# ArduinoUhr_VFD_2.net
KiCad netlist of a schematic drawn in EAGLE
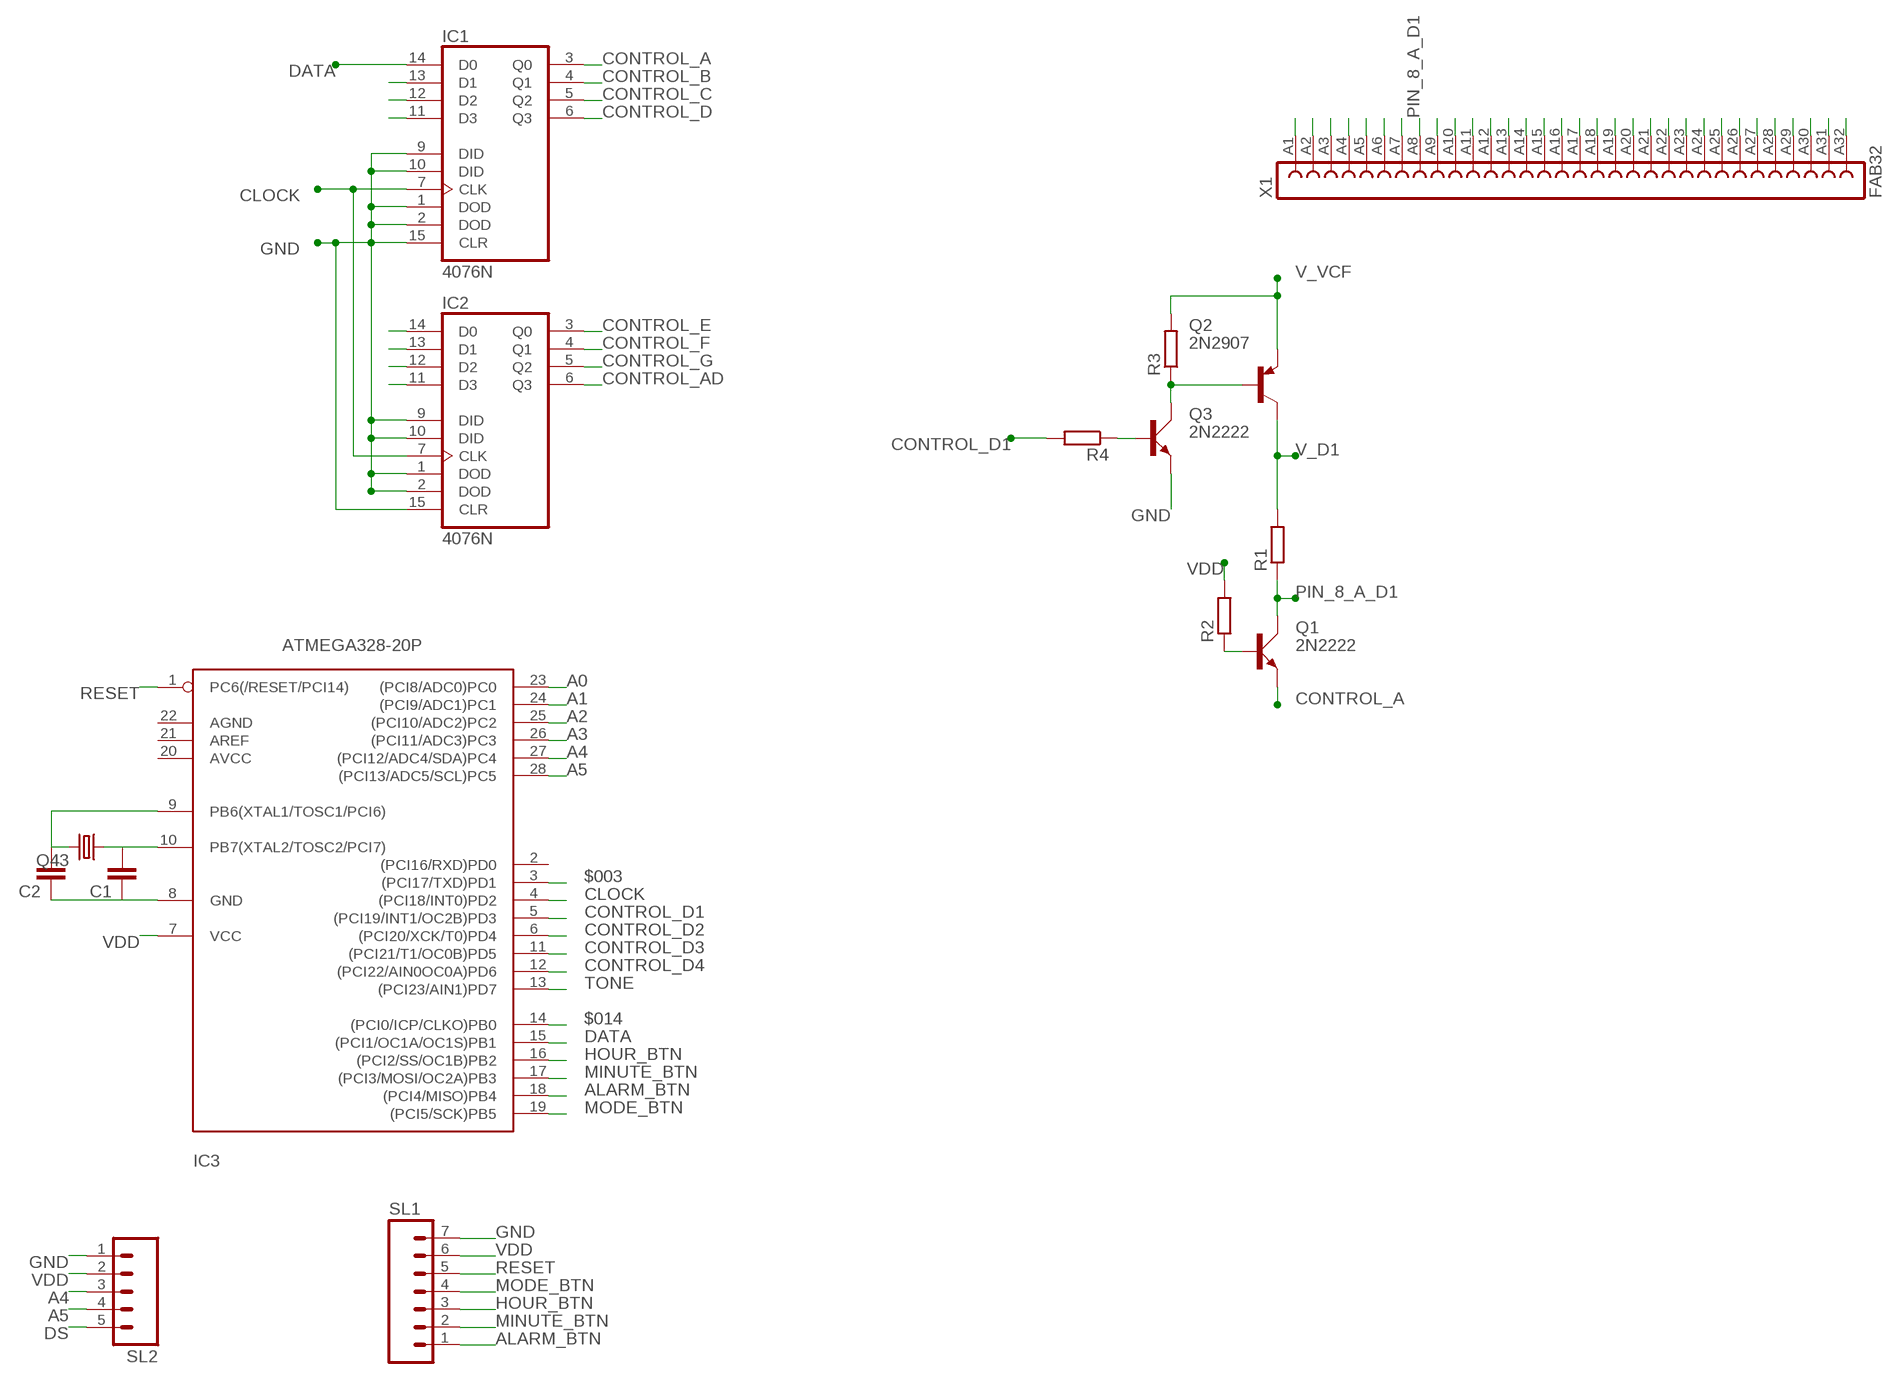
[diagram p0: schematic, sheet 1]

(export (version "E")
  (design (tool "Eeschema 10.0.6"))
  (components
    (comp (ref "C1")
      (value "C-EU025-024X044")
      (footprint "eagle-import:C025-024X044")
      (libsource (lib "eagle-import") (part "C-EU025-024X044"))
    )
    (comp (ref "C2")
      (value "C-EU025-024X044")
      (footprint "eagle-import:C025-024X044")
      (libsource (lib "eagle-import") (part "C-EU025-024X044"))
    )
    (comp (ref "IC1")
      (value "4076N")
      (footprint "eagle-import:DIL16")
      (libsource (lib "eagle-import") (part "4076N"))
    )
    (comp (ref "IC2")
      (value "4076N")
      (footprint "eagle-import:DIL16")
      (libsource (lib "eagle-import") (part "4076N"))
    )
    (comp (ref "IC3")
      (value "ATMEGA328-20P")
      (footprint "eagle-import:DIL28-3")
      (libsource (lib "eagle-import") (part "ATMEGA328P-20"))
    )
    (comp (ref "Q1")
      (value "2N2222")
      (footprint "eagle-import:TO18A")
      (libsource (lib "eagle-import") (part "2N2222"))
    )
    (comp (ref "Q2")
      (value "2N2907")
      (footprint "eagle-import:TO18")
      (libsource (lib "eagle-import") (part "2N2907"))
    )
    (comp (ref "Q3")
      (value "2N2222")
      (footprint "eagle-import:TO18A")
      (libsource (lib "eagle-import") (part "2N2222"))
    )
    (comp (ref "Q43")
      (value "CRYSTALHC49S")
      (footprint "eagle-import:HC49_S")
      (libsource (lib "eagle-import") (part "CRYSTALHC49S"))
    )
    (comp (ref "R1")
      (value "R-EU_0204/7")
      (footprint "eagle-import:0204_7")
      (libsource (lib "eagle-import") (part "R-EU_0204/7"))
    )
    (comp (ref "R2")
      (value "R-EU_0204/7")
      (footprint "eagle-import:0204_7")
      (libsource (lib "eagle-import") (part "R-EU_0204/7"))
    )
    (comp (ref "R3")
      (value "R-EU_0204/7")
      (footprint "eagle-import:0204_7")
      (libsource (lib "eagle-import") (part "R-EU_0204/7"))
    )
    (comp (ref "R4")
      (value "R-EU_0204/7")
      (footprint "eagle-import:0204_7")
      (libsource (lib "eagle-import") (part "R-EU_0204/7"))
    )
    (comp (ref "SL1")
      (value "M07")
      (footprint "eagle-import:07P")
      (libsource (lib "eagle-import") (part "M07"))
    )
    (comp (ref "SL2")
      (value "M05")
      (footprint "eagle-import:05P")
      (libsource (lib "eagle-import") (part "M05"))
    )
    (comp (ref "X1")
      (value "FAB32")
      (footprint "eagle-import:FAB32")
      (libsource (lib "eagle-import") (part "FAB32"))
    )
  )
  (nets
    (net (code "1") (name "/$003") (class "Default")
      (node (ref "IC3") (pin "3") (pinfunction "(PCI17/TXD)PD1_3") (pintype "bidirectional"))
    )
    (net (code "2") (name "/$014") (class "Default")
      (node (ref "IC3") (pin "14") (pinfunction "(PCI0/ICP/CLKO)PB0_14") (pintype "bidirectional"))
    )
    (net (code "3") (name "/A0") (class "Default")
      (node (ref "IC3") (pin "23") (pinfunction "(PCI8/ADC0)PC0_23") (pintype "bidirectional"))
    )
    (net (code "4") (name "/A1") (class "Default")
      (node (ref "IC3") (pin "24") (pinfunction "(PCI9/ADC1)PC1_24") (pintype "bidirectional"))
    )
    (net (code "5") (name "/A2") (class "Default")
      (node (ref "IC3") (pin "25") (pinfunction "(PCI10/ADC2)PC2_25") (pintype "bidirectional"))
    )
    (net (code "6") (name "/A3") (class "Default")
      (node (ref "IC3") (pin "26") (pinfunction "(PCI11/ADC3)PC3_26") (pintype "bidirectional"))
    )
    (net (code "7") (name "/A4") (class "Default")
      (node (ref "IC3") (pin "27") (pinfunction "(PCI12/ADC4/SDA)PC4_27") (pintype "bidirectional"))
      (node (ref "SL2") (pin "3") (pinfunction "3_3") (pintype "passive"))
    )
    (net (code "8") (name "/A5") (class "Default")
      (node (ref "IC3") (pin "28") (pinfunction "(PCI13/ADC5/SCL)PC5_28") (pintype "bidirectional"))
      (node (ref "SL2") (pin "4") (pinfunction "4_4") (pintype "passive"))
    )
    (net (code "9") (name "/ALARM_BTN") (class "Default")
      (node (ref "IC3") (pin "18") (pinfunction "(PCI4/MISO)PB4_18") (pintype "bidirectional"))
      (node (ref "SL1") (pin "1") (pinfunction "1_1") (pintype "passive"))
    )
    (net (code "10") (name "/CLOCK") (class "Default")
      (node (ref "IC1") (pin "7") (pinfunction "CLK_7") (pintype "input"))
      (node (ref "IC2") (pin "7") (pinfunction "CLK_7") (pintype "input"))
      (node (ref "IC3") (pin "4") (pinfunction "(PCI18/INT0)PD2_4") (pintype "bidirectional"))
    )
    (net (code "11") (name "/CONTROL_A") (class "Default")
      (node (ref "IC1") (pin "13") (pinfunction "D1_13") (pintype "input"))
      (node (ref "IC1") (pin "3") (pinfunction "Q0_3") (pintype "output"))
      (node (ref "Q1") (pin "E") (pinfunction "E_E") (pintype "passive"))
    )
    (net (code "12") (name "/CONTROL_AD") (class "Default")
      (node (ref "IC2") (pin "6") (pinfunction "Q3_6") (pintype "output"))
    )
    (net (code "13") (name "/CONTROL_B") (class "Default")
      (node (ref "IC1") (pin "12") (pinfunction "D2_12") (pintype "input"))
      (node (ref "IC1") (pin "4") (pinfunction "Q1_4") (pintype "output"))
    )
    (net (code "14") (name "/CONTROL_C") (class "Default")
      (node (ref "IC1") (pin "11") (pinfunction "D3_11") (pintype "input"))
      (node (ref "IC1") (pin "5") (pinfunction "Q2_5") (pintype "output"))
    )
    (net (code "15") (name "/CONTROL_D") (class "Default")
      (node (ref "IC1") (pin "6") (pinfunction "Q3_6") (pintype "output"))
      (node (ref "IC2") (pin "14") (pinfunction "D0_14") (pintype "input"))
    )
    (net (code "16") (name "/CONTROL_D1") (class "Default")
      (node (ref "IC3") (pin "5") (pinfunction "(PCI19/INT1/OC2B)PD3_5") (pintype "bidirectional"))
      (node (ref "R4") (pin "2") (pinfunction "2_2") (pintype "passive"))
    )
    (net (code "17") (name "/CONTROL_D2") (class "Default")
      (node (ref "IC3") (pin "6") (pinfunction "(PCI20/XCK/T0)PD4_6") (pintype "bidirectional"))
    )
    (net (code "18") (name "/CONTROL_D3") (class "Default")
      (node (ref "IC3") (pin "11") (pinfunction "(PCI21/T1/OC0B)PD5_11") (pintype "bidirectional"))
    )
    (net (code "19") (name "/CONTROL_D4") (class "Default")
      (node (ref "IC3") (pin "12") (pinfunction "(PCI22/AIN0OC0A)PD6_12") (pintype "bidirectional"))
    )
    (net (code "20") (name "/CONTROL_E") (class "Default")
      (node (ref "IC2") (pin "13") (pinfunction "D1_13") (pintype "input"))
      (node (ref "IC2") (pin "3") (pinfunction "Q0_3") (pintype "output"))
    )
    (net (code "21") (name "/CONTROL_F") (class "Default")
      (node (ref "IC2") (pin "12") (pinfunction "D2_12") (pintype "input"))
      (node (ref "IC2") (pin "4") (pinfunction "Q1_4") (pintype "output"))
    )
    (net (code "22") (name "/CONTROL_G") (class "Default")
      (node (ref "IC2") (pin "11") (pinfunction "D3_11") (pintype "input"))
      (node (ref "IC2") (pin "5") (pinfunction "Q2_5") (pintype "output"))
    )
    (net (code "23") (name "/DATA") (class "Default")
      (node (ref "IC1") (pin "14") (pinfunction "D0_14") (pintype "input"))
      (node (ref "IC3") (pin "15") (pinfunction "(PCI1/OC1A/OC1S)PB1_15") (pintype "bidirectional"))
    )
    (net (code "24") (name "/DS") (class "Default")
      (node (ref "SL2") (pin "5") (pinfunction "5_5") (pintype "passive"))
    )
    (net (code "25") (name "/GND") (class "Default")
      (node (ref "C1") (pin "1") (pinfunction "1_1") (pintype "passive"))
      (node (ref "C2") (pin "1") (pinfunction "1_1") (pintype "passive"))
      (node (ref "IC1") (pin "1") (pinfunction "DOD_1") (pintype "input"))
      (node (ref "IC1") (pin "10") (pinfunction "DID_10") (pintype "input"))
      (node (ref "IC1") (pin "15") (pinfunction "CLR_15") (pintype "input"))
      (node (ref "IC1") (pin "2") (pinfunction "DOD_2") (pintype "input"))
      (node (ref "IC1") (pin "9") (pinfunction "DID_9") (pintype "input"))
      (node (ref "IC2") (pin "1") (pinfunction "DOD_1") (pintype "input"))
      (node (ref "IC2") (pin "10") (pinfunction "DID_10") (pintype "input"))
      (node (ref "IC2") (pin "15") (pinfunction "CLR_15") (pintype "input"))
      (node (ref "IC2") (pin "2") (pinfunction "DOD_2") (pintype "input"))
      (node (ref "IC2") (pin "9") (pinfunction "DID_9") (pintype "input"))
      (node (ref "IC3") (pin "8") (pinfunction "GND_8") (pintype "bidirectional"))
      (node (ref "Q3") (pin "E") (pinfunction "E_E") (pintype "passive"))
      (node (ref "SL1") (pin "7") (pinfunction "7_7") (pintype "passive"))
      (node (ref "SL2") (pin "1") (pinfunction "1_1") (pintype "passive"))
    )
    (net (code "26") (name "/HOUR_BTN") (class "Default")
      (node (ref "IC3") (pin "16") (pinfunction "(PCI2/SS/OC1B)PB2_16") (pintype "bidirectional"))
      (node (ref "SL1") (pin "3") (pinfunction "3_3") (pintype "passive"))
    )
    (net (code "27") (name "/MINUTE_BTN") (class "Default")
      (node (ref "IC3") (pin "17") (pinfunction "(PCI3/MOSI/OC2A)PB3_17") (pintype "bidirectional"))
      (node (ref "SL1") (pin "2") (pinfunction "2_2") (pintype "passive"))
    )
    (net (code "28") (name "/MODE_BTN") (class "Default")
      (node (ref "IC3") (pin "19") (pinfunction "(PCI5/SCK)PB5_19") (pintype "bidirectional"))
      (node (ref "SL1") (pin "4") (pinfunction "4_4") (pintype "passive"))
    )
    (net (code "29") (name "/PIN_8_A_D1") (class "Default")
      (node (ref "Q1") (pin "C") (pinfunction "C_C") (pintype "passive"))
      (node (ref "R1") (pin "1") (pinfunction "1_1") (pintype "passive"))
      (node (ref "X1") (pin "A8") (pinfunction "8_A8") (pintype "passive"))
    )
    (net (code "30") (name "/RESET") (class "Default")
      (node (ref "IC3") (pin "1") (pinfunction "PC6(/RESET/PCI14)_1") (pintype "bidirectional"))
      (node (ref "SL1") (pin "5") (pinfunction "5_5") (pintype "passive"))
    )
    (net (code "31") (name "/TONE") (class "Default")
      (node (ref "IC3") (pin "13") (pinfunction "(PCI23/AIN1)PD7_13") (pintype "bidirectional"))
    )
    (net (code "32") (name "/VDD") (class "Default")
      (node (ref "IC3") (pin "7") (pinfunction "VCC_7") (pintype "bidirectional"))
      (node (ref "R2") (pin "2") (pinfunction "2_2") (pintype "passive"))
      (node (ref "SL1") (pin "6") (pinfunction "6_6") (pintype "passive"))
      (node (ref "SL2") (pin "2") (pinfunction "2_2") (pintype "passive"))
    )
    (net (code "33") (name "/V_D1") (class "Default")
      (node (ref "Q2") (pin "3") (pinfunction "C_3") (pintype "passive"))
      (node (ref "R1") (pin "2") (pinfunction "2_2") (pintype "passive"))
    )
    (net (code "34") (name "/V_VCF") (class "Default")
      (node (ref "Q2") (pin "1") (pinfunction "E_1") (pintype "passive"))
      (node (ref "R3") (pin "2") (pinfunction "2_2") (pintype "passive"))
    )
    (net (code "35") (name "Net-(IC3-PB6(XTAL1{slash}TOSC1{slash}PCI6))") (class "Default")
      (node (ref "C2") (pin "2") (pinfunction "2_2") (pintype "passive"))
      (node (ref "IC3") (pin "9") (pinfunction "PB6(XTAL1/TOSC1/PCI6)_9") (pintype "bidirectional"))
      (node (ref "Q43") (pin "2") (pinfunction "2_2") (pintype "passive"))
    )
    (net (code "36") (name "Net-(IC3-PB7(XTAL2{slash}TOSC2{slash}PCI7))") (class "Default")
      (node (ref "C1") (pin "2") (pinfunction "2_2") (pintype "passive"))
      (node (ref "IC3") (pin "10") (pinfunction "PB7(XTAL2/TOSC2/PCI7)_10") (pintype "bidirectional"))
      (node (ref "Q43") (pin "1") (pinfunction "1_1") (pintype "passive"))
    )
    (net (code "37") (name "Net-(Q1-PadB)") (class "Default")
      (node (ref "Q1") (pin "B") (pinfunction "B_B") (pintype "passive"))
      (node (ref "R2") (pin "1") (pinfunction "1_1") (pintype "passive"))
    )
    (net (code "38") (name "Net-(Q2-B)") (class "Default")
      (node (ref "Q2") (pin "2") (pinfunction "B_2") (pintype "passive"))
      (node (ref "Q3") (pin "C") (pinfunction "C_C") (pintype "passive"))
      (node (ref "R3") (pin "1") (pinfunction "1_1") (pintype "passive"))
    )
    (net (code "39") (name "Net-(Q3-PadB)") (class "Default")
      (node (ref "Q3") (pin "B") (pinfunction "B_B") (pintype "passive"))
      (node (ref "R4") (pin "1") (pinfunction "1_1") (pintype "passive"))
    )
    (net (code "40") (name "unconnected-(IC3-(PCI16{slash}RXD)PD0-Pad2)") (class "Default")
      (node (ref "IC3") (pin "2") (pinfunction "(PCI16/RXD)PD0_2") (pintype "bidirectional"))
    )
    (net (code "41") (name "unconnected-(IC3-AGND-Pad22)") (class "Default")
      (node (ref "IC3") (pin "22") (pinfunction "AGND_22") (pintype "bidirectional"))
    )
    (net (code "42") (name "unconnected-(IC3-AREF-Pad21)") (class "Default")
      (node (ref "IC3") (pin "21") (pinfunction "AREF_21") (pintype "bidirectional"))
    )
    (net (code "43") (name "unconnected-(IC3-AVCC-Pad20)") (class "Default")
      (node (ref "IC3") (pin "20") (pinfunction "AVCC_20") (pintype "bidirectional"))
    )
    (net (code "44") (name "unconnected-(X1-1-PadA1)") (class "Default")
      (node (ref "X1") (pin "A1") (pinfunction "1_A1") (pintype "passive"))
    )
    (net (code "45") (name "unconnected-(X1-2-PadA2)") (class "Default")
      (node (ref "X1") (pin "A2") (pinfunction "2_A2") (pintype "passive"))
    )
    (net (code "46") (name "unconnected-(X1-3-PadA3)") (class "Default")
      (node (ref "X1") (pin "A3") (pinfunction "3_A3") (pintype "passive"))
    )
    (net (code "47") (name "unconnected-(X1-4-PadA4)") (class "Default")
      (node (ref "X1") (pin "A4") (pinfunction "4_A4") (pintype "passive"))
    )
    (net (code "48") (name "unconnected-(X1-5-PadA5)") (class "Default")
      (node (ref "X1") (pin "A5") (pinfunction "5_A5") (pintype "passive"))
    )
    (net (code "49") (name "unconnected-(X1-6-PadA6)") (class "Default")
      (node (ref "X1") (pin "A6") (pinfunction "6_A6") (pintype "passive"))
    )
    (net (code "50") (name "unconnected-(X1-7-PadA7)") (class "Default")
      (node (ref "X1") (pin "A7") (pinfunction "7_A7") (pintype "passive"))
    )
    (net (code "51") (name "unconnected-(X1-9-PadA9)") (class "Default")
      (node (ref "X1") (pin "A9") (pinfunction "9_A9") (pintype "passive"))
    )
    (net (code "52") (name "unconnected-(X1-10-PadA10)") (class "Default")
      (node (ref "X1") (pin "A10") (pinfunction "10_A10") (pintype "passive"))
    )
    (net (code "53") (name "unconnected-(X1-11-PadA11)") (class "Default")
      (node (ref "X1") (pin "A11") (pinfunction "11_A11") (pintype "passive"))
    )
    (net (code "54") (name "unconnected-(X1-12-PadA12)") (class "Default")
      (node (ref "X1") (pin "A12") (pinfunction "12_A12") (pintype "passive"))
    )
    (net (code "55") (name "unconnected-(X1-13-PadA13)") (class "Default")
      (node (ref "X1") (pin "A13") (pinfunction "13_A13") (pintype "passive"))
    )
    (net (code "56") (name "unconnected-(X1-14-PadA14)") (class "Default")
      (node (ref "X1") (pin "A14") (pinfunction "14_A14") (pintype "passive"))
    )
    (net (code "57") (name "unconnected-(X1-15-PadA15)") (class "Default")
      (node (ref "X1") (pin "A15") (pinfunction "15_A15") (pintype "passive"))
    )
    (net (code "58") (name "unconnected-(X1-16-PadA16)") (class "Default")
      (node (ref "X1") (pin "A16") (pinfunction "16_A16") (pintype "passive"))
    )
    (net (code "59") (name "unconnected-(X1-17-PadA17)") (class "Default")
      (node (ref "X1") (pin "A17") (pinfunction "17_A17") (pintype "passive"))
    )
    (net (code "60") (name "unconnected-(X1-18-PadA18)") (class "Default")
      (node (ref "X1") (pin "A18") (pinfunction "18_A18") (pintype "passive"))
    )
    (net (code "61") (name "unconnected-(X1-19-PadA19)") (class "Default")
      (node (ref "X1") (pin "A19") (pinfunction "19_A19") (pintype "passive"))
    )
    (net (code "62") (name "unconnected-(X1-20-PadA20)") (class "Default")
      (node (ref "X1") (pin "A20") (pinfunction "20_A20") (pintype "passive"))
    )
    (net (code "63") (name "unconnected-(X1-21-PadA21)") (class "Default")
      (node (ref "X1") (pin "A21") (pinfunction "21_A21") (pintype "passive"))
    )
    (net (code "64") (name "unconnected-(X1-22-PadA22)") (class "Default")
      (node (ref "X1") (pin "A22") (pinfunction "22_A22") (pintype "passive"))
    )
    (net (code "65") (name "unconnected-(X1-23-PadA23)") (class "Default")
      (node (ref "X1") (pin "A23") (pinfunction "23_A23") (pintype "passive"))
    )
    (net (code "66") (name "unconnected-(X1-24-PadA24)") (class "Default")
      (node (ref "X1") (pin "A24") (pinfunction "24_A24") (pintype "passive"))
    )
    (net (code "67") (name "unconnected-(X1-25-PadA25)") (class "Default")
      (node (ref "X1") (pin "A25") (pinfunction "25_A25") (pintype "passive"))
    )
    (net (code "68") (name "unconnected-(X1-26-PadA26)") (class "Default")
      (node (ref "X1") (pin "A26") (pinfunction "26_A26") (pintype "passive"))
    )
    (net (code "69") (name "unconnected-(X1-27-PadA27)") (class "Default")
      (node (ref "X1") (pin "A27") (pinfunction "27_A27") (pintype "passive"))
    )
    (net (code "70") (name "unconnected-(X1-28-PadA28)") (class "Default")
      (node (ref "X1") (pin "A28") (pinfunction "28_A28") (pintype "passive"))
    )
    (net (code "71") (name "unconnected-(X1-29-PadA29)") (class "Default")
      (node (ref "X1") (pin "A29") (pinfunction "29_A29") (pintype "passive"))
    )
    (net (code "72") (name "unconnected-(X1-30-PadA30)") (class "Default")
      (node (ref "X1") (pin "A30") (pinfunction "30_A30") (pintype "passive"))
    )
    (net (code "73") (name "unconnected-(X1-31-PadA31)") (class "Default")
      (node (ref "X1") (pin "A31") (pinfunction "31_A31") (pintype "passive"))
    )
    (net (code "74") (name "unconnected-(X1-32-PadA32)") (class "Default")
      (node (ref "X1") (pin "A32") (pinfunction "32_A32") (pintype "passive"))
    )
  )
)
